# DS18B20_with_DS2480B_MAX233_V3.net
KiCad netlist of a schematic drawn in EAGLE
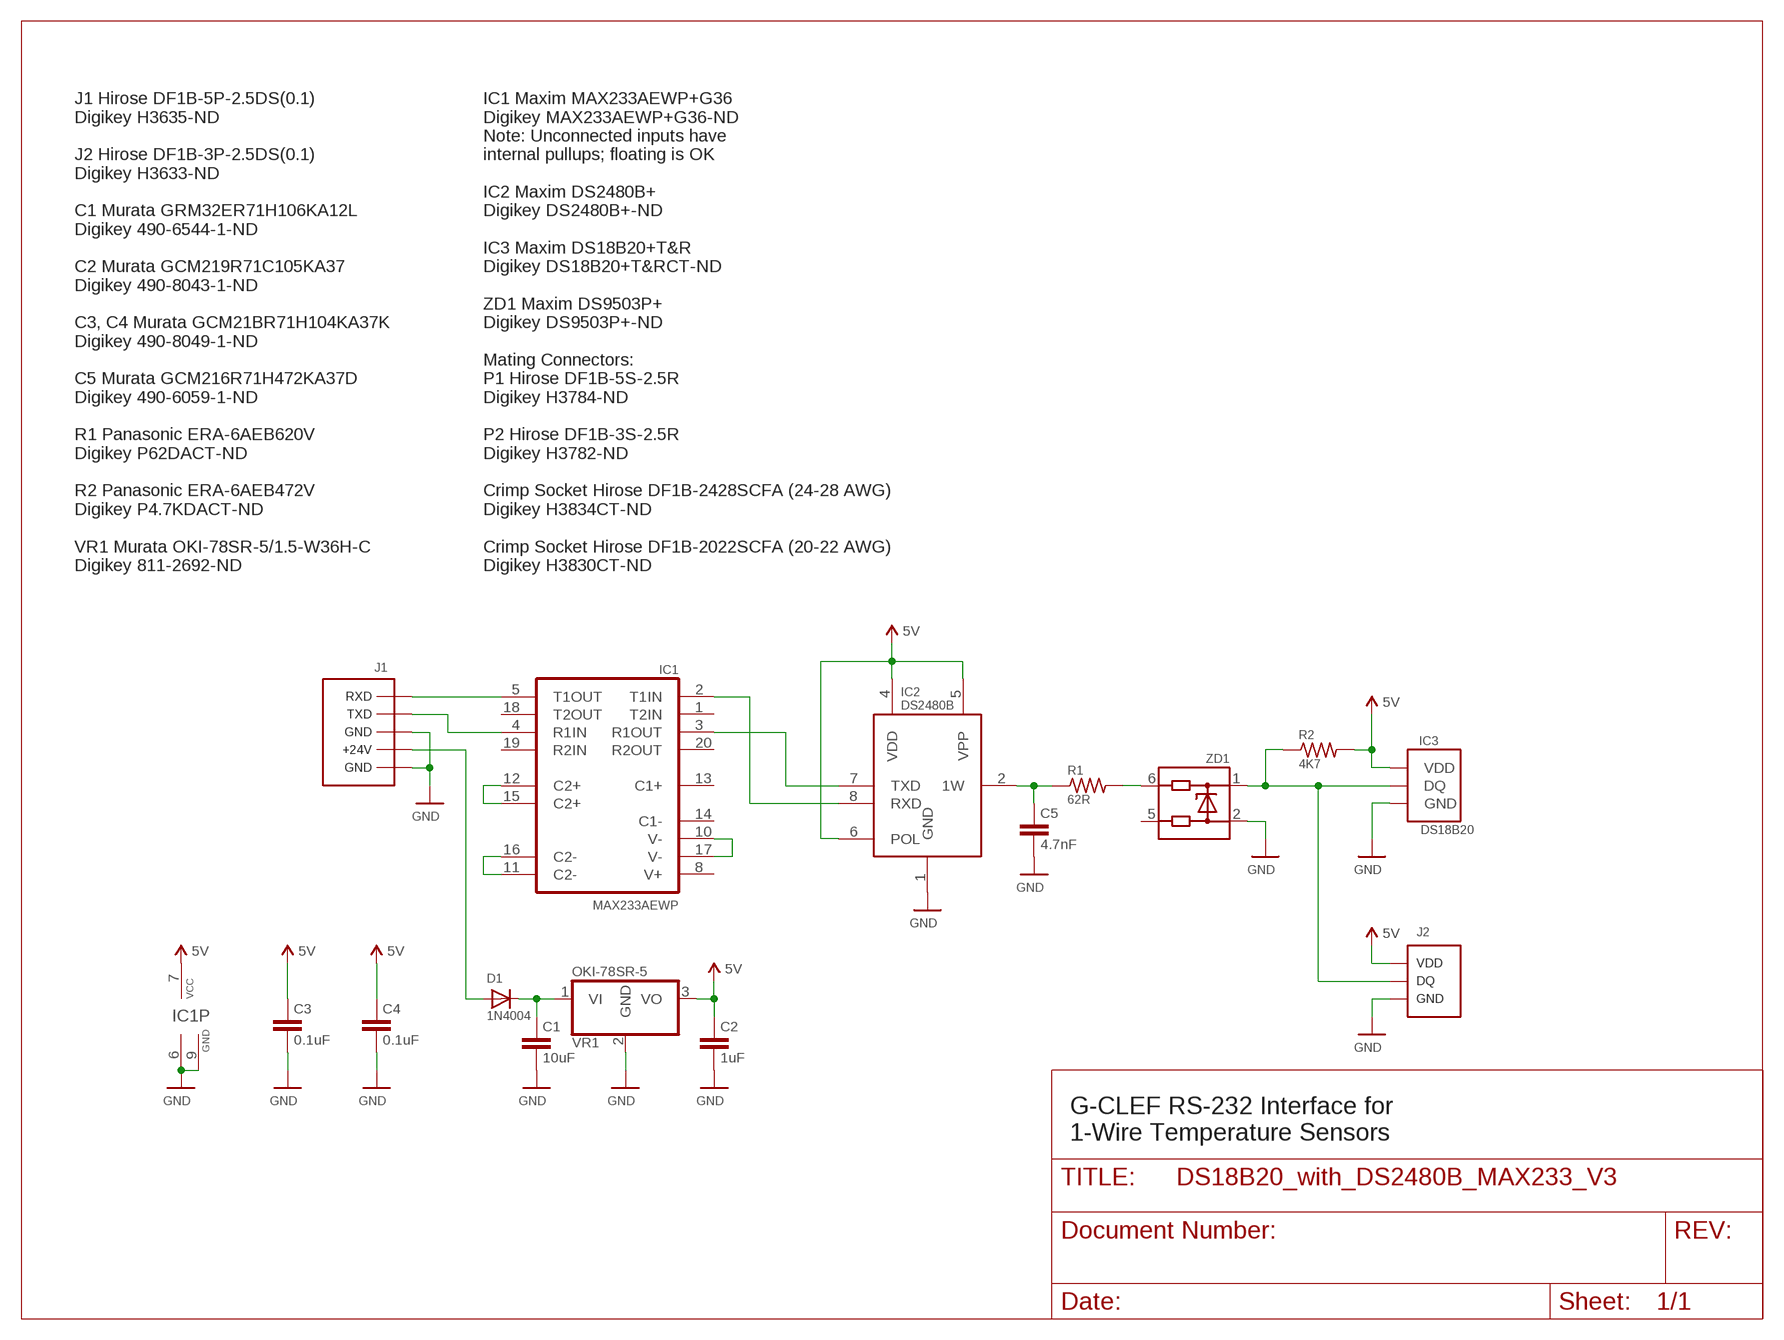
[diagram p0: schematic, sheet 1]

(export (version "E")
  (design (tool "Eeschema 10.0.6"))
  (components
    (comp (ref "C1")
      (value "10uF")
      (footprint "eagle-import:CAPC3225X270N")
      (libsource (lib "eagle-import") (part "C-UNPOL1210-CAP"))
    )
    (comp (ref "C2")
      (value "1uF")
      (footprint "eagle-import:CAPC2013X135N")
      (libsource (lib "eagle-import") (part "C-UNPOL0805-CAP"))
    )
    (comp (ref "C3")
      (value "0.1uF")
      (footprint "eagle-import:CAPC2013X135N")
      (libsource (lib "eagle-import") (part "C-UNPOL0805-CAP"))
    )
    (comp (ref "C4")
      (value "0.1uF")
      (footprint "eagle-import:CAPC2013X135N")
      (libsource (lib "eagle-import") (part "C-UNPOL0805-CAP"))
    )
    (comp (ref "C5")
      (value "4.7nF")
      (footprint "eagle-import:CAPC2013X135N")
      (libsource (lib "eagle-import") (part "C-UNPOL0805-CAP"))
    )
    (comp (ref "D1")
      (value "1N4004")
      (footprint "eagle-import:DO41-10")
      (libsource (lib "eagle-import") (part "1N4004"))
    )
    (comp (ref "IC1")
      (value "MAX233AEWP")
      (footprint "eagle-import:SO20L")
      (fields (field (name "MPN") "MAX233AEWP+G36"))
      (libsource (lib "eagle-import") (part "MAX233AEWP"))
    )
    (comp (ref "IC2")
      (value "DS2480B")
      (footprint "eagle-import:SO08")
      (libsource (lib "eagle-import") (part "DS2480B"))
    )
    (comp (ref "IC3")
      (value "DS18B20")
      (footprint "eagle-import:TO92-")
      (libsource (lib "eagle-import") (part "DS18B20"))
    )
    (comp (ref "J1")
      (value "DF1B-5P")
      (footprint "eagle-import:DF1B-5P")
      (libsource (lib "eagle-import") (part "DF1B-5P"))
    )
    (comp (ref "J2")
      (value "DF1B-3P")
      (footprint "eagle-import:DF1B-3P")
      (libsource (lib "eagle-import") (part "DF1B-3P"))
    )
    (comp (ref "R1")
      (value "62R")
      (footprint "eagle-import:RESISTOR-0805")
      (libsource (lib "eagle-import") (part "RESISTOR-0805"))
    )
    (comp (ref "R2")
      (value "4K7")
      (footprint "eagle-import:RESISTOR-0805")
      (libsource (lib "eagle-import") (part "RESISTOR-0805"))
    )
    (comp (ref "VR1")
      (value "OKI-78SR-5")
      (footprint "eagle-import:OKI-78SR")
      (libsource (lib "eagle-import") (part "OKI-78SRH"))
    )
    (comp (ref "ZD1")
      (value "DS9503P")
      (footprint "eagle-import:TSOC6+")
      (libsource (lib "eagle-import") (part "DS9503P"))
    )
  )
  (nets
    (net (code "1") (name "5V") (class "Default")
      (node (ref "C2") (pin "1") (pinfunction "1_1") (pintype "passive"))
      (node (ref "C3") (pin "1") (pinfunction "1_1") (pintype "passive"))
      (node (ref "C4") (pin "1") (pinfunction "1_1") (pintype "passive"))
      (node (ref "IC1") (pin "7") (pinfunction "VCC_7") (pintype "power_in"))
      (node (ref "IC2") (pin "4") (pinfunction "VDD_4") (pintype "power_in"))
      (node (ref "IC2") (pin "5") (pinfunction "VPP_5") (pintype "power_in"))
      (node (ref "IC2") (pin "6") (pinfunction "POL_6") (pintype "input"))
      (node (ref "IC3") (pin "3") (pinfunction "VDD_3") (pintype "bidirectional"))
      (node (ref "J2") (pin "P$3") (pinfunction "P$3_P$3") (pintype "bidirectional"))
      (node (ref "R2") (pin "2") (pinfunction "2_2") (pintype "passive"))
      (node (ref "VR1") (pin "3") (pinfunction "VO_3") (pintype "passive"))
    )
    (net (code "2") (name "GND") (class "Default")
      (node (ref "C1") (pin "2") (pinfunction "2_2") (pintype "passive"))
      (node (ref "C2") (pin "2") (pinfunction "2_2") (pintype "passive"))
      (node (ref "C3") (pin "2") (pinfunction "2_2") (pintype "passive"))
      (node (ref "C4") (pin "2") (pinfunction "2_2") (pintype "passive"))
      (node (ref "C5") (pin "2") (pinfunction "2_2") (pintype "passive"))
      (node (ref "IC1") (pin "6") (pinfunction "GND_6") (pintype "power_in"))
      (node (ref "IC1") (pin "9") (pinfunction "GND_9") (pintype "power_in"))
      (node (ref "IC2") (pin "1") (pinfunction "GND_1") (pintype "power_in"))
      (node (ref "IC3") (pin "1") (pinfunction "GND_1") (pintype "bidirectional"))
      (node (ref "J1") (pin "P$1") (pinfunction "P$1_P$1") (pintype "bidirectional"))
      (node (ref "J1") (pin "P$3") (pinfunction "P$3_P$3") (pintype "bidirectional"))
      (node (ref "J2") (pin "P$1") (pinfunction "P$1_P$1") (pintype "bidirectional"))
      (node (ref "VR1") (pin "2") (pinfunction "GND_2") (pintype "passive"))
      (node (ref "ZD1") (pin "2") (pinfunction "P$2_2") (pintype "passive"))
    )
    (net (code "3") (name "Net-(D1-PadA)") (class "Default")
      (node (ref "D1") (pin "A") (pinfunction "A_A") (pintype "passive"))
      (node (ref "J1") (pin "P$2") (pinfunction "P$2_P$2") (pintype "bidirectional"))
    )
    (net (code "4") (name "Net-(IC1A-C2+-Pad12)") (class "Default")
      (node (ref "IC1") (pin "12") (pinfunction "C2+_12") (pintype "bidirectional"))
      (node (ref "IC1") (pin "15") (pinfunction "C2+_15") (pintype "bidirectional"))
    )
    (net (code "5") (name "Net-(IC1A-C2--Pad11)") (class "Default")
      (node (ref "IC1") (pin "11") (pinfunction "C2-_11") (pintype "bidirectional"))
      (node (ref "IC1") (pin "16") (pinfunction "C2-_16") (pintype "bidirectional"))
    )
    (net (code "6") (name "Net-(IC1A-R1IN)") (class "Default")
      (node (ref "IC1") (pin "4") (pinfunction "R1IN_4") (pintype "input"))
      (node (ref "J1") (pin "P$4") (pinfunction "P$4_P$4") (pintype "bidirectional"))
    )
    (net (code "7") (name "Net-(IC1A-R1OUT)") (class "Default")
      (node (ref "IC1") (pin "3") (pinfunction "R1OUT_3") (pintype "output"))
      (node (ref "IC2") (pin "7") (pinfunction "TXD_7") (pintype "input"))
    )
    (net (code "8") (name "Net-(IC1A-T1IN)") (class "Default")
      (node (ref "IC1") (pin "2") (pinfunction "T1IN_2") (pintype "input"))
      (node (ref "IC2") (pin "8") (pinfunction "RXD_8") (pintype "output"))
    )
    (net (code "9") (name "Net-(IC1A-T1OUT)") (class "Default")
      (node (ref "IC1") (pin "5") (pinfunction "T1OUT_5") (pintype "output"))
      (node (ref "J1") (pin "P$5") (pinfunction "P$5_P$5") (pintype "bidirectional"))
    )
    (net (code "10") (name "Net-(IC1A-V--Pad10)") (class "Default")
      (node (ref "IC1") (pin "10") (pinfunction "V-_10") (pintype "bidirectional"))
      (node (ref "IC1") (pin "17") (pinfunction "V-_17") (pintype "bidirectional"))
    )
    (net (code "11") (name "Net-(IC2-1W)") (class "Default")
      (node (ref "C5") (pin "1") (pinfunction "1_1") (pintype "passive"))
      (node (ref "IC2") (pin "2") (pinfunction "1W_2") (pintype "open_collector"))
      (node (ref "R1") (pin "1") (pinfunction "1_1") (pintype "passive"))
    )
    (net (code "12") (name "Net-(IC3-DQ)") (class "Default")
      (node (ref "IC3") (pin "2") (pinfunction "DQ_2") (pintype "bidirectional"))
      (node (ref "J2") (pin "P$2") (pinfunction "P$2_P$2") (pintype "bidirectional"))
      (node (ref "R2") (pin "1") (pinfunction "1_1") (pintype "passive"))
      (node (ref "ZD1") (pin "1") (pinfunction "P$1_1") (pintype "passive"))
    )
    (net (code "13") (name "Net-(VR1-VI)") (class "Default")
      (node (ref "C1") (pin "1") (pinfunction "1_1") (pintype "passive"))
      (node (ref "D1") (pin "C") (pinfunction "C_C") (pintype "passive"))
      (node (ref "VR1") (pin "1") (pinfunction "VI_1") (pintype "input"))
    )
    (net (code "14") (name "Net-(ZD1-P$4)") (class "Default")
      (node (ref "R1") (pin "2") (pinfunction "2_2") (pintype "passive"))
      (node (ref "ZD1") (pin "6") (pinfunction "P$4_6") (pintype "passive"))
    )
    (net (code "15") (name "unconnected-(IC1A-C1+-Pad13)") (class "Default")
      (node (ref "IC1") (pin "13") (pinfunction "C1+_13") (pintype "bidirectional"))
    )
    (net (code "16") (name "unconnected-(IC1A-C1--Pad14)") (class "Default")
      (node (ref "IC1") (pin "14") (pinfunction "C1-_14") (pintype "bidirectional"))
    )
    (net (code "17") (name "unconnected-(IC1A-R2IN-Pad19)") (class "Default")
      (node (ref "IC1") (pin "19") (pinfunction "R2IN_19") (pintype "input"))
    )
    (net (code "18") (name "unconnected-(IC1A-R2OUT-Pad20)") (class "Default")
      (node (ref "IC1") (pin "20") (pinfunction "R2OUT_20") (pintype "output"))
    )
    (net (code "19") (name "unconnected-(IC1A-T2IN-Pad1)") (class "Default")
      (node (ref "IC1") (pin "1") (pinfunction "T2IN_1") (pintype "input"))
    )
    (net (code "20") (name "unconnected-(IC1A-T2OUT-Pad18)") (class "Default")
      (node (ref "IC1") (pin "18") (pinfunction "T2OUT_18") (pintype "output"))
    )
    (net (code "21") (name "unconnected-(IC1A-V+-Pad8)") (class "Default")
      (node (ref "IC1") (pin "8") (pinfunction "V+_8") (pintype "bidirectional"))
    )
    (net (code "22") (name "unconnected-(ZD1-P$3-Pad5)") (class "Default")
      (node (ref "ZD1") (pin "5") (pinfunction "P$3_5") (pintype "passive"))
    )
  )
)
